# T03_MotionControledLampLedDriver.net
KiCad netlist of a schematic drawn in EAGLE
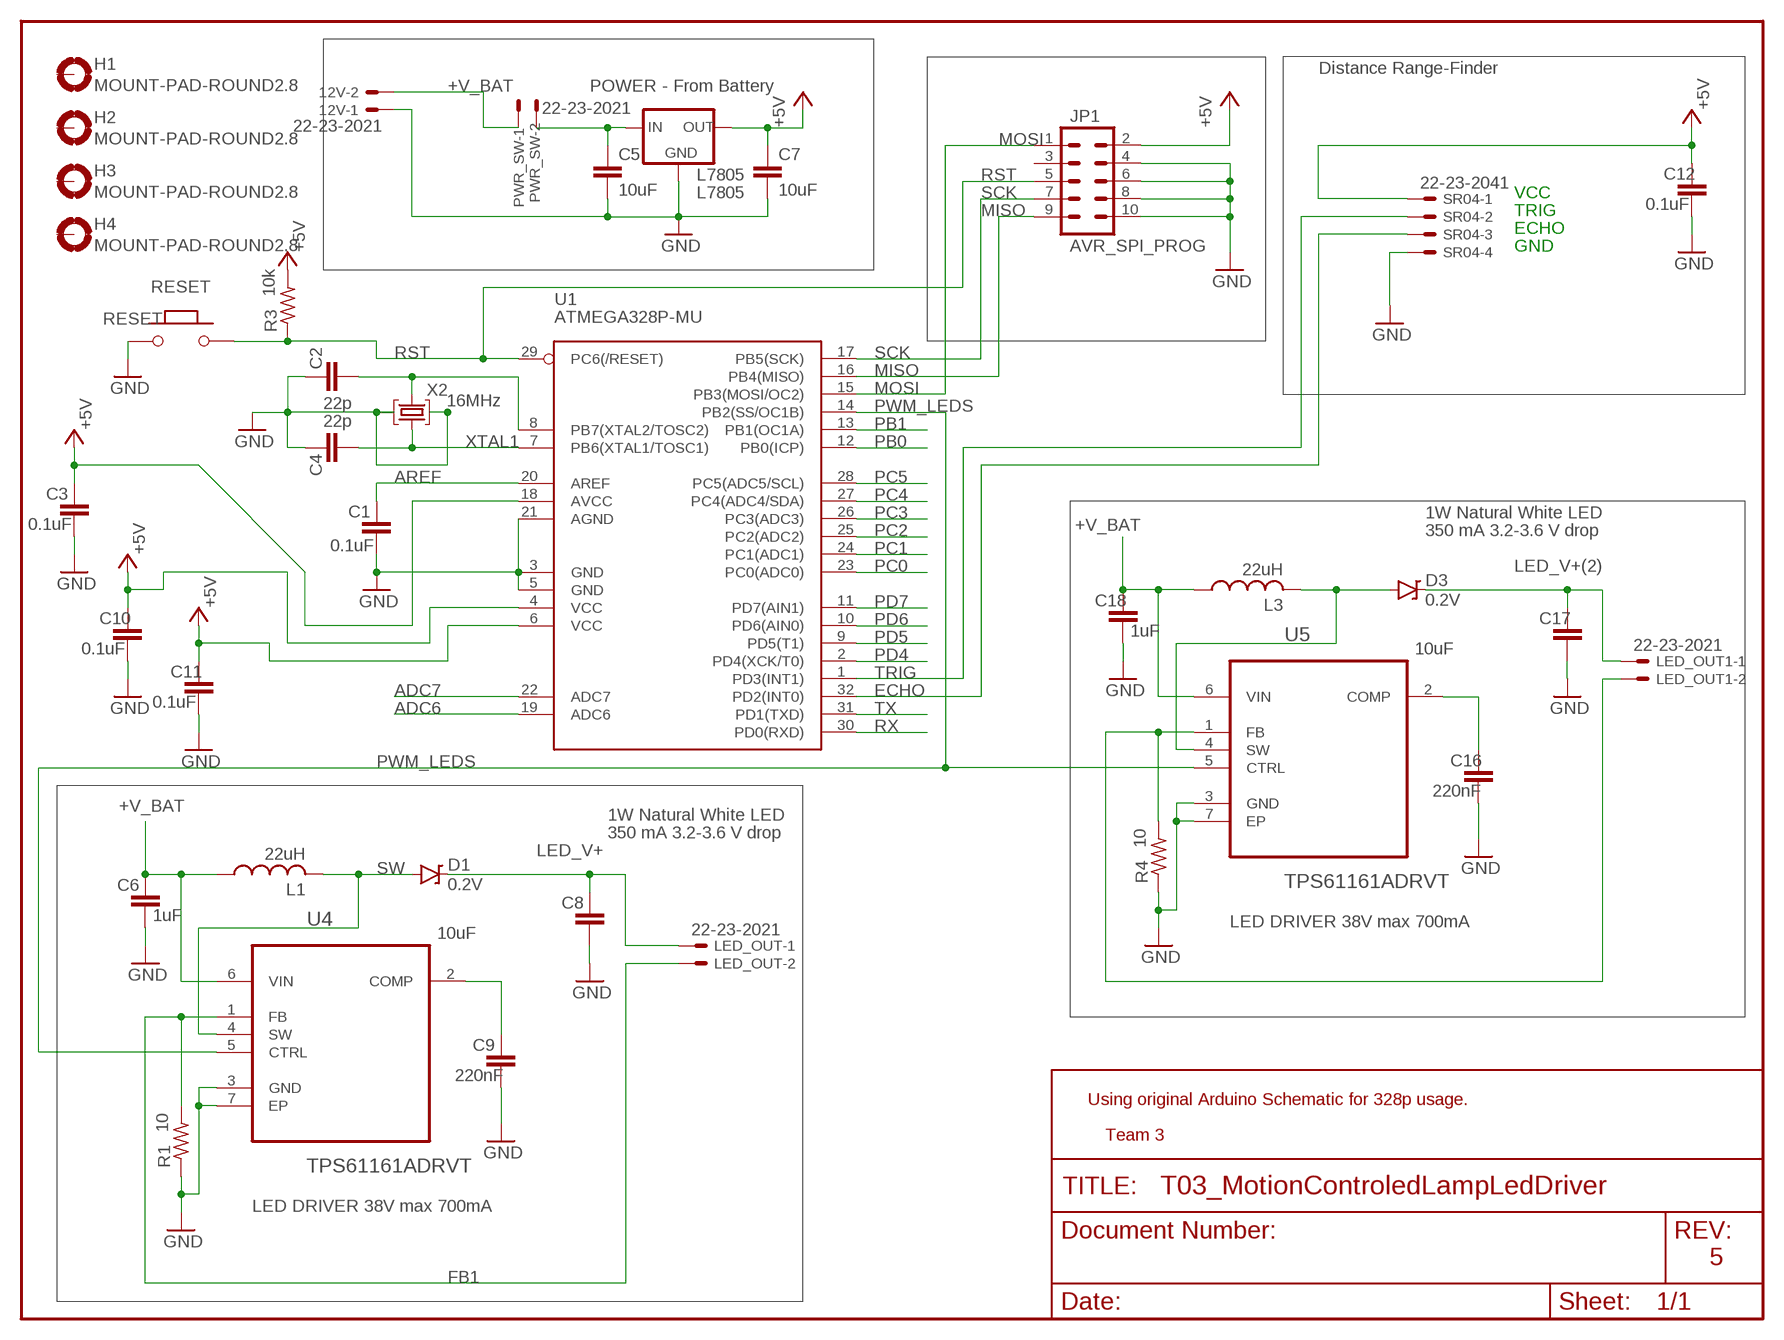
[diagram p0: schematic, sheet 1]

(export (version "E")
  (design (tool "Eeschema 10.0.6"))
  (components
    (comp (ref "12V")
      (value "22-23-2021")
      (footprint "eagle-import:22-23-2021")
      (fields (field (name "MF") "MOLEX"))
      (libsource (lib "eagle-import") (part "22-23-2021"))
    )
    (comp (ref "C1")
      (value "0.1uF")
      (footprint "eagle-import:C0603-ROUND")
      (libsource (lib "eagle-import") (part "C-EUC0603"))
    )
    (comp (ref "C2")
      (value "22p")
      (footprint "eagle-import:C0603-ROUND")
      (libsource (lib "eagle-import") (part "C-EUC0603"))
    )
    (comp (ref "C3")
      (value "0.1uF")
      (footprint "eagle-import:C0603-ROUND")
      (libsource (lib "eagle-import") (part "C-EUC0603"))
    )
    (comp (ref "C4")
      (value "22p")
      (footprint "eagle-import:C0603-ROUND")
      (libsource (lib "eagle-import") (part "C-EUC0603"))
    )
    (comp (ref "C5")
      (value "10uF")
      (footprint "eagle-import:C1206")
      (libsource (lib "eagle-import") (part "rcl_C-EUC1206"))
    )
    (comp (ref "C6")
      (value "1uF")
      (footprint "eagle-import:C0603-ROUND")
      (libsource (lib "eagle-import") (part "C-EUC0603"))
    )
    (comp (ref "C7")
      (value "10uF")
      (footprint "eagle-import:C1206")
      (libsource (lib "eagle-import") (part "rcl_C-EUC1206"))
    )
    (comp (ref "C8")
      (value "10uF")
      (footprint "eagle-import:C0603-ROUND")
      (libsource (lib "eagle-import") (part "C-EUC0603"))
    )
    (comp (ref "C9")
      (value "220nF")
      (footprint "eagle-import:C0603-ROUND")
      (libsource (lib "eagle-import") (part "C-EUC0603"))
    )
    (comp (ref "C10")
      (value "0.1uF")
      (footprint "eagle-import:C0603-ROUND")
      (libsource (lib "eagle-import") (part "C-EUC0603"))
    )
    (comp (ref "C11")
      (value "0.1uF")
      (footprint "eagle-import:C0603-ROUND")
      (libsource (lib "eagle-import") (part "C-EUC0603"))
    )
    (comp (ref "C12")
      (value "0.1uF")
      (footprint "eagle-import:C0603-ROUND")
      (libsource (lib "eagle-import") (part "C-EUC0603"))
    )
    (comp (ref "C16")
      (value "220nF")
      (footprint "eagle-import:C0603-ROUND")
      (libsource (lib "eagle-import") (part "C-EUC0603"))
    )
    (comp (ref "C17")
      (value "10uF")
      (footprint "eagle-import:C0603-ROUND")
      (libsource (lib "eagle-import") (part "C-EUC0603"))
    )
    (comp (ref "C18")
      (value "1uF")
      (footprint "eagle-import:C0603-ROUND")
      (libsource (lib "eagle-import") (part "C-EUC0603"))
    )
    (comp (ref "D1")
      (value "0.2V")
      (footprint "eagle-import:SOD-323")
      (libsource (lib "eagle-import") (part "DIODE-ZENER3.3V"))
    )
    (comp (ref "D3")
      (value "0.2V")
      (footprint "eagle-import:SOD-323")
      (libsource (lib "eagle-import") (part "DIODE-ZENER3.3V"))
    )
    (comp (ref "H1")
      (value "MOUNT-PAD-ROUND2.8")
      (footprint "eagle-import:2,8-PAD")
      (libsource (lib "eagle-import") (part "MOUNT-PAD-ROUND2.8"))
    )
    (comp (ref "H2")
      (value "MOUNT-PAD-ROUND2.8")
      (footprint "eagle-import:2,8-PAD")
      (libsource (lib "eagle-import") (part "MOUNT-PAD-ROUND2.8"))
    )
    (comp (ref "H3")
      (value "MOUNT-PAD-ROUND2.8")
      (footprint "eagle-import:2,8-PAD")
      (libsource (lib "eagle-import") (part "MOUNT-PAD-ROUND2.8"))
    )
    (comp (ref "H4")
      (value "MOUNT-PAD-ROUND2.8")
      (footprint "eagle-import:2,8-PAD")
      (libsource (lib "eagle-import") (part "MOUNT-PAD-ROUND2.8"))
    )
    (comp (ref "JP1")
      (value "AVR_SPI_PROG")
      (footprint "eagle-import:2X5-SHROUDED_LOCK")
      (libsource (lib "eagle-import") (part "M05X2SHD_LOCK"))
    )
    (comp (ref "L1")
      (value "22uH")
      (footprint "eagle-import:L4532P")
      (libsource (lib "eagle-import") (part "L-USL4532P"))
    )
    (comp (ref "L3")
      (value "22uH")
      (footprint "eagle-import:L4532P")
      (libsource (lib "eagle-import") (part "L-USL4532P"))
    )
    (comp (ref "L7805")
      (value "L7805")
      (footprint "eagle-import:78XXL")
      (libsource (lib "eagle-import") (part "78XXL"))
    )
    (comp (ref "LED_OUT")
      (value "22-23-2021")
      (footprint "eagle-import:22-23-2021")
      (fields (field (name "MF") "MOLEX"))
      (libsource (lib "eagle-import") (part "22-23-2021"))
    )
    (comp (ref "LED_OUT1")
      (value "22-23-2021")
      (footprint "eagle-import:22-23-2021")
      (fields (field (name "MF") "MOLEX"))
      (libsource (lib "eagle-import") (part "22-23-2021"))
    )
    (comp (ref "PWR_SW")
      (value "22-23-2021")
      (footprint "eagle-import:22-23-2021")
      (fields (field (name "MF") "MOLEX"))
      (libsource (lib "eagle-import") (part "22-23-2021"))
    )
    (comp (ref "R1")
      (value "10")
      (footprint "eagle-import:M1206")
      (libsource (lib "eagle-import") (part "R-US_M1206"))
    )
    (comp (ref "R3")
      (value "10k")
      (footprint "eagle-import:M1206")
      (libsource (lib "eagle-import") (part "R-US_M1206"))
    )
    (comp (ref "R4")
      (value "10")
      (footprint "eagle-import:M1206")
      (libsource (lib "eagle-import") (part "R-US_M1206"))
    )
    (comp (ref "RESET")
      (value "RESET")
      (footprint "eagle-import:SMD_157SW")
      (libsource (lib "eagle-import") (part "MYSMD_PB157"))
    )
    (comp (ref "SR04")
      (value "22-23-2041")
      (footprint "eagle-import:22-23-2041")
      (fields (field (name "MF") "MOLEX"))
      (libsource (lib "eagle-import") (part "22-23-2041"))
    )
    (comp (ref "U1")
      (value "ATMEGA328P-MU")
      (footprint "eagle-import:TQFP32-08")
      (libsource (lib "eagle-import") (part "ATMEGAXX8-AU"))
    )
    (comp (ref "U4")
      (value "TPS61161ADRVT")
      (footprint "eagle-import:SON65P200X200X80-7N")
      (libsource (lib "eagle-import") (part "TPS61161ADRVT"))
    )
    (comp (ref "U5")
      (value "TPS61161ADRVT")
      (footprint "eagle-import:SON65P200X200X80-7N")
      (libsource (lib "eagle-import") (part "TPS61161ADRVT"))
    )
    (comp (ref "X2")
      (value "16MHz")
      (footprint "eagle-import:CRYSTAL-3.2-2.5")
      (libsource (lib "eagle-import") (part "CRYSTAL-3.2-2.5"))
    )
  )
  (nets
    (net (code "1") (name "+5V") (class "Default")
      (node (ref "C10") (pin "2") (pinfunction "2_2") (pintype "passive"))
      (node (ref "C11") (pin "2") (pinfunction "2_2") (pintype "passive"))
      (node (ref "C12") (pin "2") (pinfunction "2_2") (pintype "passive"))
      (node (ref "C3") (pin "2") (pinfunction "2_2") (pintype "passive"))
      (node (ref "C7") (pin "1") (pinfunction "1_1") (pintype "passive"))
      (node (ref "JP1") (pin "2") (pinfunction "2_2") (pintype "passive"))
      (node (ref "L7805") (pin "OUT") (pinfunction "OUT_OUT") (pintype "passive"))
      (node (ref "R3") (pin "2") (pinfunction "2_2") (pintype "passive"))
      (node (ref "SR04") (pin "1") (pinfunction "S_1") (pintype "passive"))
      (node (ref "U1") (pin "18") (pinfunction "AVCC_18") (pintype "bidirectional"))
      (node (ref "U1") (pin "4") (pinfunction "VCC_4") (pintype "bidirectional"))
      (node (ref "U1") (pin "6") (pinfunction "VCC_6") (pintype "bidirectional"))
    )
    (net (code "2") (name "/+V_BAT") (class "Default")
      (node (ref "12V") (pin "2") (pinfunction "S_2") (pintype "passive"))
      (node (ref "C18") (pin "2") (pinfunction "2_2") (pintype "passive"))
      (node (ref "C6") (pin "2") (pinfunction "2_2") (pintype "passive"))
      (node (ref "L1") (pin "1") (pinfunction "1_1") (pintype "passive"))
      (node (ref "L3") (pin "1") (pinfunction "1_1") (pintype "passive"))
      (node (ref "PWR_SW") (pin "1") (pinfunction "S_1") (pintype "passive"))
      (node (ref "U4") (pin "6") (pinfunction "VIN_6") (pintype "power_in"))
      (node (ref "U5") (pin "6") (pinfunction "VIN_6") (pintype "power_in"))
    )
    (net (code "3") (name "/ADC6") (class "Default")
      (node (ref "U1") (pin "19") (pinfunction "ADC6_19") (pintype "bidirectional"))
    )
    (net (code "4") (name "/ADC7") (class "Default")
      (node (ref "U1") (pin "22") (pinfunction "ADC7_22") (pintype "bidirectional"))
    )
    (net (code "5") (name "/AREF") (class "Default")
      (node (ref "C1") (pin "2") (pinfunction "2_2") (pintype "passive"))
      (node (ref "U1") (pin "20") (pinfunction "AREF_20") (pintype "bidirectional"))
    )
    (net (code "6") (name "/ECHO") (class "Default")
      (node (ref "SR04") (pin "3") (pinfunction "S_3") (pintype "passive"))
      (node (ref "U1") (pin "32") (pinfunction "PD2(INT0)_32") (pintype "bidirectional"))
    )
    (net (code "7") (name "/FB1") (class "Default")
      (node (ref "LED_OUT") (pin "2") (pinfunction "S_2") (pintype "passive"))
      (node (ref "R1") (pin "2") (pinfunction "2_2") (pintype "passive"))
      (node (ref "U4") (pin "1") (pinfunction "FB_1") (pintype "input"))
    )
    (net (code "8") (name "/LED_V+") (class "Default")
      (node (ref "C8") (pin "2") (pinfunction "2_2") (pintype "passive"))
      (node (ref "D1") (pin "C") (pinfunction "C_C") (pintype "passive"))
      (node (ref "LED_OUT") (pin "1") (pinfunction "S_1") (pintype "passive"))
    )
    (net (code "9") (name "/LED_V+(2)") (class "Default")
      (node (ref "C17") (pin "2") (pinfunction "2_2") (pintype "passive"))
      (node (ref "D3") (pin "C") (pinfunction "C_C") (pintype "passive"))
      (node (ref "LED_OUT1") (pin "1") (pinfunction "S_1") (pintype "passive"))
    )
    (net (code "10") (name "/MISO") (class "Default")
      (node (ref "JP1") (pin "9") (pinfunction "9_9") (pintype "passive"))
      (node (ref "U1") (pin "16") (pinfunction "PB4(MISO)_16") (pintype "bidirectional"))
    )
    (net (code "11") (name "/MOSI") (class "Default")
      (node (ref "JP1") (pin "1") (pinfunction "1_1") (pintype "passive"))
      (node (ref "U1") (pin "15") (pinfunction "PB3(MOSI/OC2)_15") (pintype "bidirectional"))
    )
    (net (code "12") (name "/PB0") (class "Default")
      (node (ref "U1") (pin "12") (pinfunction "PB0(ICP)_12") (pintype "bidirectional"))
    )
    (net (code "13") (name "/PB1") (class "Default")
      (node (ref "U1") (pin "13") (pinfunction "PB1(OC1A)_13") (pintype "bidirectional"))
    )
    (net (code "14") (name "/PC0") (class "Default")
      (node (ref "U1") (pin "23") (pinfunction "PC0(ADC0)_23") (pintype "bidirectional"))
    )
    (net (code "15") (name "/PC1") (class "Default")
      (node (ref "U1") (pin "24") (pinfunction "PC1(ADC1)_24") (pintype "bidirectional"))
    )
    (net (code "16") (name "/PC2") (class "Default")
      (node (ref "U1") (pin "25") (pinfunction "PC2(ADC2)_25") (pintype "bidirectional"))
    )
    (net (code "17") (name "/PC3") (class "Default")
      (node (ref "U1") (pin "26") (pinfunction "PC3(ADC3)_26") (pintype "bidirectional"))
    )
    (net (code "18") (name "/PC4") (class "Default")
      (node (ref "U1") (pin "27") (pinfunction "PC4(ADC4/SDA)_27") (pintype "bidirectional"))
    )
    (net (code "19") (name "/PC5") (class "Default")
      (node (ref "U1") (pin "28") (pinfunction "PC5(ADC5/SCL)_28") (pintype "bidirectional"))
    )
    (net (code "20") (name "/PD4") (class "Default")
      (node (ref "U1") (pin "2") (pinfunction "PD4(XCK/T0)_2") (pintype "bidirectional"))
    )
    (net (code "21") (name "/PD5") (class "Default")
      (node (ref "U1") (pin "9") (pinfunction "PD5(T1)_9") (pintype "bidirectional"))
    )
    (net (code "22") (name "/PD6") (class "Default")
      (node (ref "U1") (pin "10") (pinfunction "PD6(AIN0)_10") (pintype "bidirectional"))
    )
    (net (code "23") (name "/PD7") (class "Default")
      (node (ref "U1") (pin "11") (pinfunction "PD7(AIN1)_11") (pintype "bidirectional"))
    )
    (net (code "24") (name "/PWM_LEDS") (class "Default")
      (node (ref "U1") (pin "14") (pinfunction "PB2(SS/OC1B)_14") (pintype "bidirectional"))
      (node (ref "U4") (pin "5") (pinfunction "CTRL_5") (pintype "input"))
      (node (ref "U5") (pin "5") (pinfunction "CTRL_5") (pintype "input"))
    )
    (net (code "25") (name "/RST") (class "Default")
      (node (ref "JP1") (pin "5") (pinfunction "5_5") (pintype "passive"))
      (node (ref "R3") (pin "1") (pinfunction "1_1") (pintype "passive"))
      (node (ref "RESET") (pin "2") (pinfunction "2_2") (pintype "passive"))
      (node (ref "U1") (pin "29") (pinfunction "PC6(/RESET)_29") (pintype "bidirectional"))
    )
    (net (code "26") (name "/RX") (class "Default")
      (node (ref "U1") (pin "30") (pinfunction "PD0(RXD)_30") (pintype "bidirectional"))
    )
    (net (code "27") (name "/SCK") (class "Default")
      (node (ref "JP1") (pin "7") (pinfunction "7_7") (pintype "passive"))
      (node (ref "U1") (pin "17") (pinfunction "PB5(SCK)_17") (pintype "bidirectional"))
    )
    (net (code "28") (name "/SW") (class "Default")
      (node (ref "D1") (pin "A") (pinfunction "A_A") (pintype "passive"))
      (node (ref "L1") (pin "2") (pinfunction "2_2") (pintype "passive"))
      (node (ref "U4") (pin "4") (pinfunction "SW_4") (pintype "input"))
    )
    (net (code "29") (name "/TRIG") (class "Default")
      (node (ref "SR04") (pin "2") (pinfunction "S_2") (pintype "passive"))
      (node (ref "U1") (pin "1") (pinfunction "PD3(INT1)_1") (pintype "bidirectional"))
    )
    (net (code "30") (name "/TX") (class "Default")
      (node (ref "U1") (pin "31") (pinfunction "PD1(TXD)_31") (pintype "bidirectional"))
    )
    (net (code "31") (name "/XTAL1") (class "Default")
      (node (ref "C4") (pin "1") (pinfunction "1_1") (pintype "passive"))
      (node (ref "U1") (pin "7") (pinfunction "PB6(XTAL1/TOSC1)_7") (pintype "bidirectional"))
      (node (ref "X2") (pin "1") (pinfunction "C1_1") (pintype "passive"))
    )
    (net (code "32") (name "GND") (class "Default")
      (node (ref "12V") (pin "1") (pinfunction "S_1") (pintype "passive"))
      (node (ref "C1") (pin "1") (pinfunction "1_1") (pintype "passive"))
      (node (ref "C10") (pin "1") (pinfunction "1_1") (pintype "passive"))
      (node (ref "C11") (pin "1") (pinfunction "1_1") (pintype "passive"))
      (node (ref "C12") (pin "1") (pinfunction "1_1") (pintype "passive"))
      (node (ref "C16") (pin "1") (pinfunction "1_1") (pintype "passive"))
      (node (ref "C17") (pin "1") (pinfunction "1_1") (pintype "passive"))
      (node (ref "C18") (pin "1") (pinfunction "1_1") (pintype "passive"))
      (node (ref "C2") (pin "2") (pinfunction "2_2") (pintype "passive"))
      (node (ref "C3") (pin "1") (pinfunction "1_1") (pintype "passive"))
      (node (ref "C4") (pin "2") (pinfunction "2_2") (pintype "passive"))
      (node (ref "C5") (pin "2") (pinfunction "2_2") (pintype "passive"))
      (node (ref "C6") (pin "1") (pinfunction "1_1") (pintype "passive"))
      (node (ref "C7") (pin "2") (pinfunction "2_2") (pintype "passive"))
      (node (ref "C8") (pin "1") (pinfunction "1_1") (pintype "passive"))
      (node (ref "C9") (pin "1") (pinfunction "1_1") (pintype "passive"))
      (node (ref "JP1") (pin "10") (pinfunction "10_10") (pintype "passive"))
      (node (ref "JP1") (pin "4") (pinfunction "4_4") (pintype "passive"))
      (node (ref "JP1") (pin "6") (pinfunction "6_6") (pintype "passive"))
      (node (ref "JP1") (pin "8") (pinfunction "8_8") (pintype "passive"))
      (node (ref "L7805") (pin "GND") (pinfunction "GND_GND") (pintype "input"))
      (node (ref "R1") (pin "1") (pinfunction "1_1") (pintype "passive"))
      (node (ref "R4") (pin "1") (pinfunction "1_1") (pintype "passive"))
      (node (ref "RESET") (pin "1") (pinfunction "1_1") (pintype "passive"))
      (node (ref "SR04") (pin "4") (pinfunction "S_4") (pintype "passive"))
      (node (ref "U1") (pin "21") (pinfunction "AGND_21") (pintype "bidirectional"))
      (node (ref "U1") (pin "3") (pinfunction "GND_3") (pintype "bidirectional"))
      (node (ref "U1") (pin "5") (pinfunction "GND_5") (pintype "bidirectional"))
      (node (ref "U4") (pin "3") (pinfunction "GND_3") (pintype "passive"))
      (node (ref "U4") (pin "7") (pinfunction "EP_7") (pintype "passive"))
      (node (ref "U5") (pin "3") (pinfunction "GND_3") (pintype "passive"))
      (node (ref "U5") (pin "7") (pinfunction "EP_7") (pintype "passive"))
      (node (ref "X2") (pin "2") (pinfunction "GND_2") (pintype "passive"))
      (node (ref "X2") (pin "4") (pinfunction "GND_4") (pintype "passive"))
    )
    (net (code "33") (name "Net-(LED_OUT1B-S)") (class "Default")
      (node (ref "LED_OUT1") (pin "2") (pinfunction "S_2") (pintype "passive"))
      (node (ref "R4") (pin "2") (pinfunction "2_2") (pintype "passive"))
      (node (ref "U5") (pin "1") (pinfunction "FB_1") (pintype "input"))
    )
    (net (code "34") (name "Net-(PWR_SWB-S)") (class "Default")
      (node (ref "C5") (pin "1") (pinfunction "1_1") (pintype "passive"))
      (node (ref "L7805") (pin "IN") (pinfunction "IN_IN") (pintype "input"))
      (node (ref "PWR_SW") (pin "2") (pinfunction "S_2") (pintype "passive"))
    )
    (net (code "35") (name "Net-(U1-PB7(XTAL2{slash}TOSC2))") (class "Default")
      (node (ref "C2") (pin "1") (pinfunction "1_1") (pintype "passive"))
      (node (ref "U1") (pin "8") (pinfunction "PB7(XTAL2/TOSC2)_8") (pintype "bidirectional"))
      (node (ref "X2") (pin "3") (pinfunction "C2_3") (pintype "passive"))
    )
    (net (code "36") (name "Net-(U4-COMP)") (class "Default")
      (node (ref "C9") (pin "2") (pinfunction "2_2") (pintype "passive"))
      (node (ref "U4") (pin "2") (pinfunction "COMP_2") (pintype "output"))
    )
    (net (code "37") (name "Net-(U5-COMP)") (class "Default")
      (node (ref "C16") (pin "2") (pinfunction "2_2") (pintype "passive"))
      (node (ref "U5") (pin "2") (pinfunction "COMP_2") (pintype "output"))
    )
    (net (code "38") (name "Net-(U5-SW)") (class "Default")
      (node (ref "D3") (pin "A") (pinfunction "A_A") (pintype "passive"))
      (node (ref "L3") (pin "2") (pinfunction "2_2") (pintype "passive"))
      (node (ref "U5") (pin "4") (pinfunction "SW_4") (pintype "input"))
    )
    (net (code "39") (name "unconnected-(H1-MOUNT-PadB2,8)") (class "Default")
      (node (ref "H1") (pin "B2,8") (pinfunction "MOUNT_B2,8") (pintype "passive"))
    )
    (net (code "40") (name "unconnected-(H2-MOUNT-PadB2,8)") (class "Default")
      (node (ref "H2") (pin "B2,8") (pinfunction "MOUNT_B2,8") (pintype "passive"))
    )
    (net (code "41") (name "unconnected-(H3-MOUNT-PadB2,8)") (class "Default")
      (node (ref "H3") (pin "B2,8") (pinfunction "MOUNT_B2,8") (pintype "passive"))
    )
    (net (code "42") (name "unconnected-(H4-MOUNT-PadB2,8)") (class "Default")
      (node (ref "H4") (pin "B2,8") (pinfunction "MOUNT_B2,8") (pintype "passive"))
    )
    (net (code "43") (name "unconnected-(JP1-Pad3)") (class "Default")
      (node (ref "JP1") (pin "3") (pinfunction "3_3") (pintype "passive"))
    )
  )
)
